# RASP_PICO_SCH.net
KiCad netlist of a schematic drawn in Altium Designer
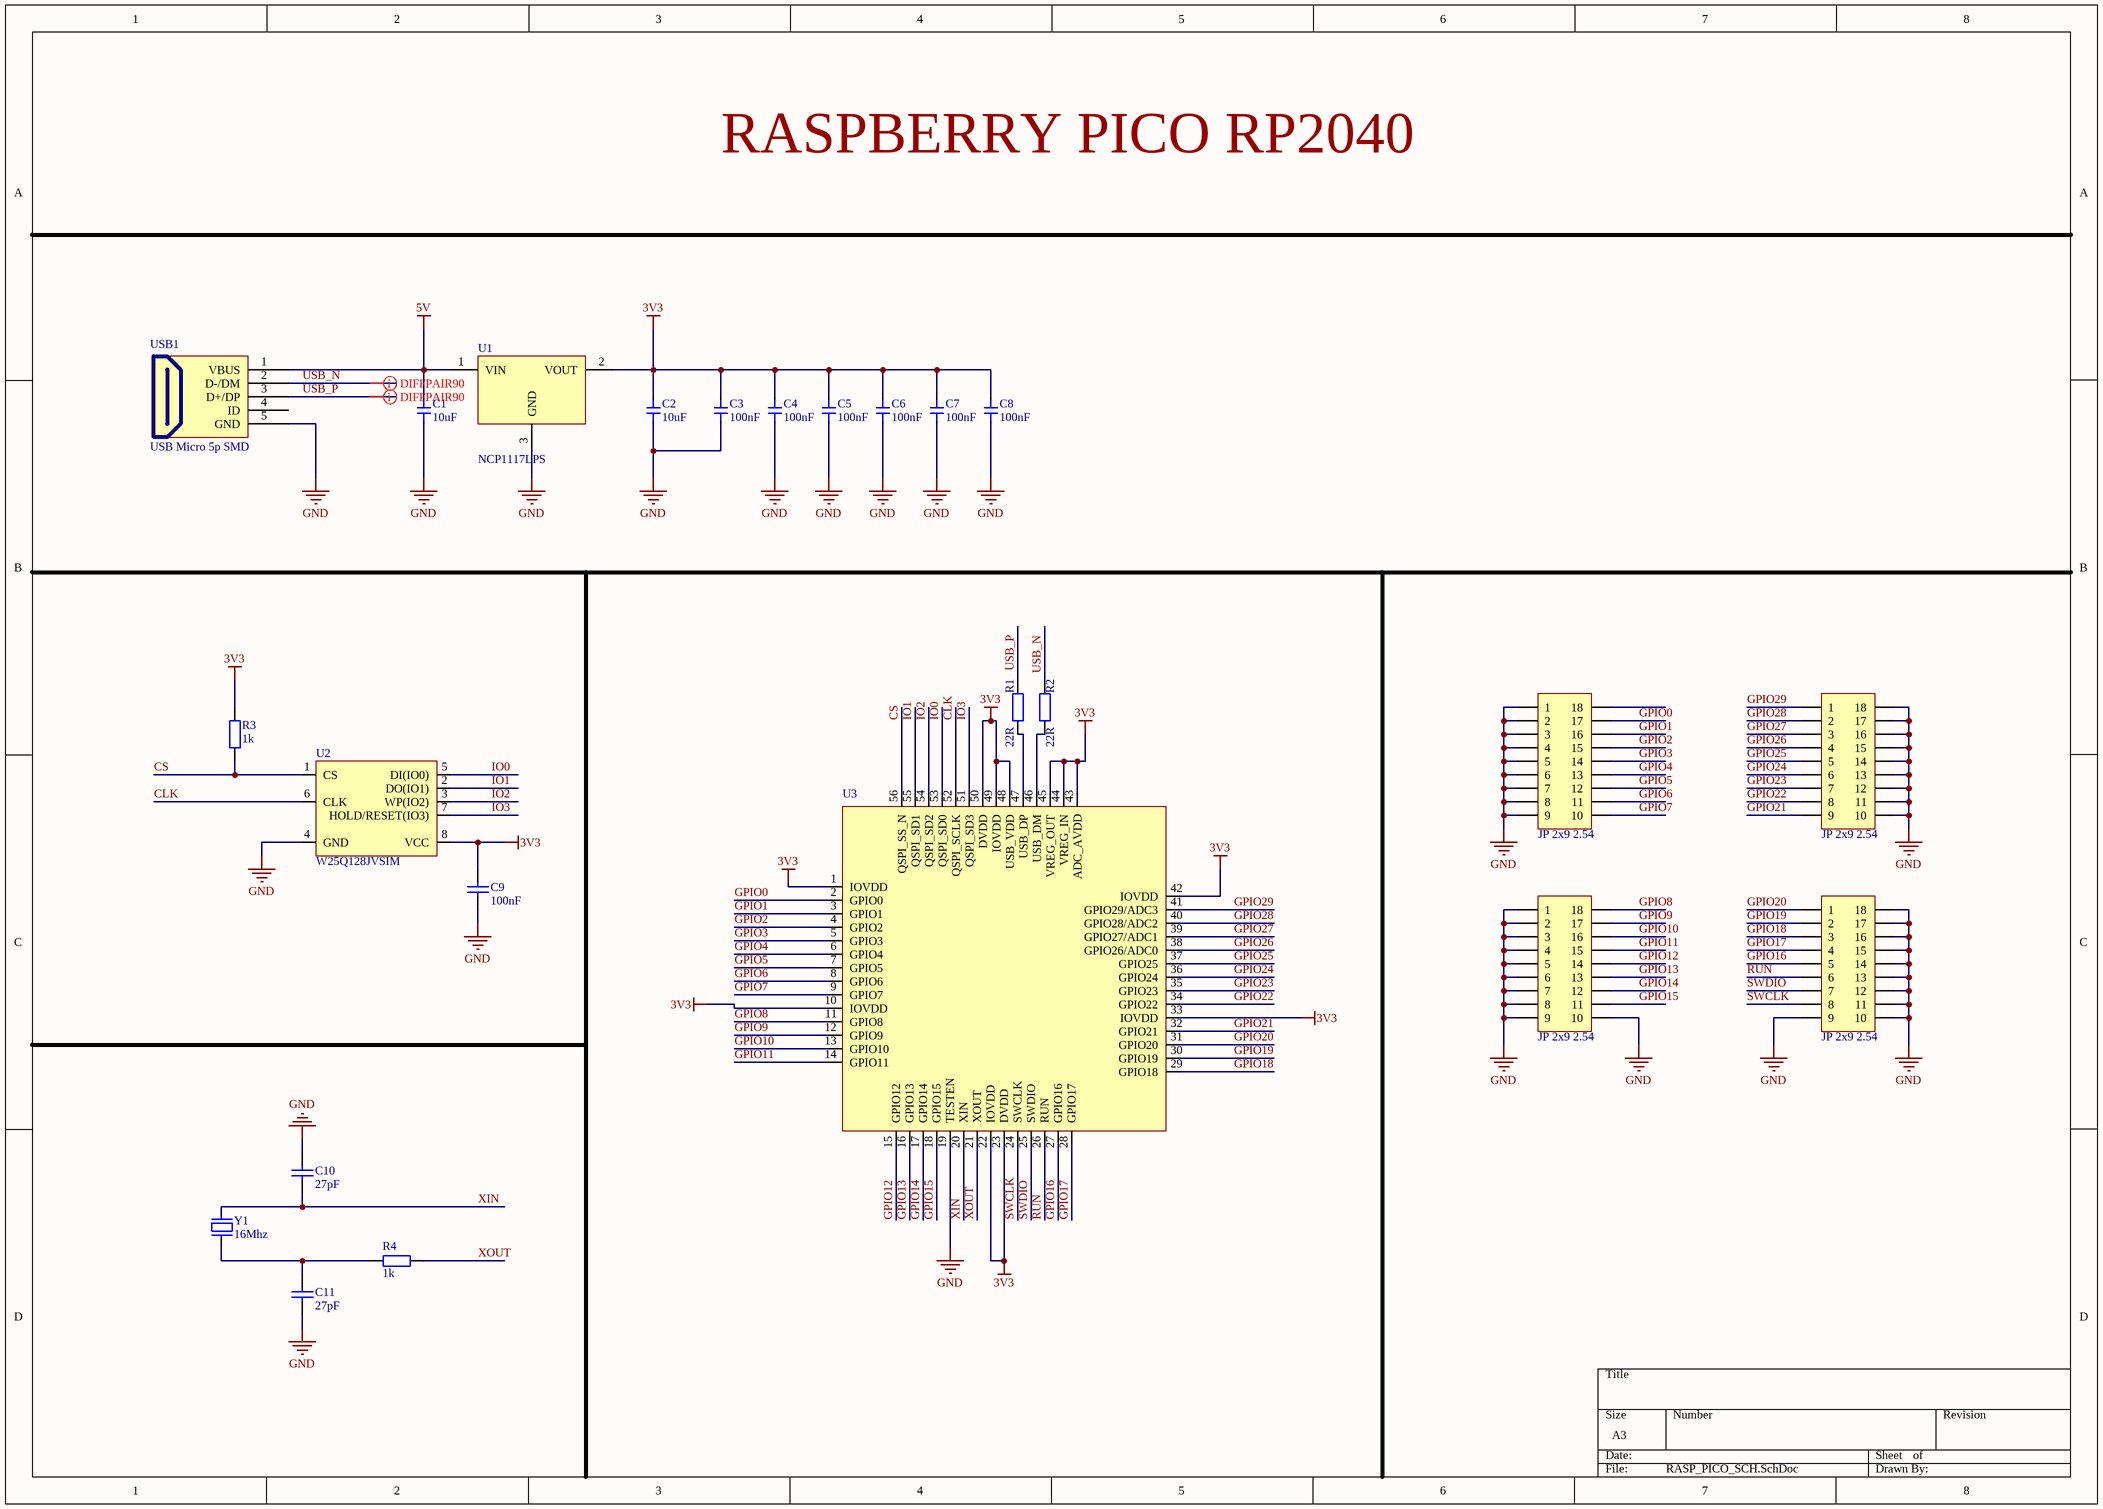
[diagram p0: RASP_PICO_SCH.SchDoc]

(export (version "E")
  (design (tool "Eeschema 10.0.6"))
  (components
    (comp (ref "C1")
      (value "10uF")
      (footprint "Cap 0805")
      (description "Capacitor SMD 0805")
      (libsource (lib "Altium_Lib_by_KhueNguyenCreator") (part "Cap 0805"))
    )
    (comp (ref "C2")
      (value "10uF")
      (footprint "Cap 0805")
      (description "Capacitor SMD 0805")
      (libsource (lib "Altium_Lib_by_KhueNguyenCreator") (part "Cap 0805"))
    )
    (comp (ref "C3")
      (value "100nF")
      (footprint "Cap 0805")
      (description "Capacitor SMD 0805")
      (libsource (lib "Altium_Lib_by_KhueNguyenCreator") (part "Cap 0805"))
    )
    (comp (ref "C4")
      (value "100nF")
      (footprint "Cap 0805")
      (description "Capacitor SMD 0805")
      (libsource (lib "Altium_Lib_by_KhueNguyenCreator") (part "Cap 0805"))
    )
    (comp (ref "C5")
      (value "100nF")
      (footprint "Cap 0805")
      (description "Capacitor SMD 0805")
      (libsource (lib "Altium_Lib_by_KhueNguyenCreator") (part "Cap 0805"))
    )
    (comp (ref "C6")
      (value "100nF")
      (footprint "Cap 0805")
      (description "Capacitor SMD 0805")
      (libsource (lib "Altium_Lib_by_KhueNguyenCreator") (part "Cap 0805"))
    )
    (comp (ref "C7")
      (value "100nF")
      (footprint "Cap 0805")
      (description "Capacitor SMD 0805")
      (libsource (lib "Altium_Lib_by_KhueNguyenCreator") (part "Cap 0805"))
    )
    (comp (ref "C8")
      (value "100nF")
      (footprint "Cap 0805")
      (description "Capacitor SMD 0805")
      (libsource (lib "Altium_Lib_by_KhueNguyenCreator") (part "Cap 0805"))
    )
    (comp (ref "C9")
      (value "100nF")
      (footprint "tu 0805")
      (description "Dán")
      (libsource (lib "Altium_Lib_by_KhueNguyenCreator") (part "Tu 0805 101 50V 20%"))
    )
    (comp (ref "C10")
      (value "27pF")
      (footprint "tu 0805")
      (description "Dán")
      (libsource (lib "Altium_Lib_by_KhueNguyenCreator") (part "Tu 0805 101 50V 20%"))
    )
    (comp (ref "C11")
      (value "27pF")
      (footprint "tu 0805")
      (description "Dán")
      (libsource (lib "Altium_Lib_by_KhueNguyenCreator") (part "Tu 0805 101 50V 20%"))
    )
    (comp (ref "JP1")
      (value "JP 2x9 2.54")
      (footprint "JP 2x9 DT")
      (description "Cắm")
      (libsource (lib "Altium_Lib_by_KhueNguyenCreator") (part "JP 2x9 2.54 Duc Thang"))
    )
    (comp (ref "JP2")
      (value "JP 2x9 2.54")
      (footprint "JP 2x9 DT")
      (description "Cắm")
      (libsource (lib "Altium_Lib_by_KhueNguyenCreator") (part "JP 2x9 2.54 Duc Thang"))
    )
    (comp (ref "JP3")
      (value "JP 2x9 2.54")
      (footprint "JP 2x9 DT")
      (description "Cắm")
      (libsource (lib "Altium_Lib_by_KhueNguyenCreator") (part "JP 2x9 2.54 Duc Thang"))
    )
    (comp (ref "JP4")
      (value "JP 2x9 2.54")
      (footprint "JP 2x9 DT")
      (description "Cắm")
      (libsource (lib "Altium_Lib_by_KhueNguyenCreator") (part "JP 2x9 2.54 Duc Thang"))
    )
    (comp (ref "R1")
      (value "22R")
      (footprint "tro smd 0805")
      (description "Dán")
      (libsource (lib "Altium_Lib_by_KhueNguyenCreator") (part "Tro 0805 5% 22R"))
    )
    (comp (ref "R2")
      (value "22R")
      (footprint "tro smd 0805")
      (description "Dán")
      (libsource (lib "Altium_Lib_by_KhueNguyenCreator") (part "Tro 0805 5% 22R"))
    )
    (comp (ref "R3")
      (value "1k")
      (footprint "tro smd 0805")
      (description "Dán")
      (libsource (lib "Altium_Lib_by_KhueNguyenCreator") (part "Tro 0805 1% 1k"))
    )
    (comp (ref "R4")
      (value "1k")
      (footprint "tro smd 0805")
      (description "Dán")
      (libsource (lib "Altium_Lib_by_KhueNguyenCreator") (part "Tro 0805 1% 1k"))
    )
    (comp (ref "U1")
      (value "NCP1117LPS")
      (footprint "SOT-223")
      (description "IC 3V3")
      (libsource (lib "SCH_LIB") (part "NCP1117LPS"))
    )
    (comp (ref "U2")
      (value "W25Q128JVSIM")
      (footprint "SOIC127P790X216-8N")
      (description "NOR Flash Serial (SPI, Dual SPI, Quad SPI) 3V/3.3V 128M-bit 16M x 8 6ns 8-Pin SOIC Tube")
      (fields (field (name "MANUFACTURER") "Winbond"))
      (libsource (lib "SCH_LIB") (part "W25Q128JVSIM"))
    )
    (comp (ref "U3")
      (value "RP2040TR7")
      (footprint "QFN40P700X700X90_HS-57N")
      (libsource (lib "SCH_LIB") (part "RP2040TR7"))
    )
    (comp (ref "USB1")
      (value "USB Micro 5p SMD")
      (footprint "USB Micro 5p SMD")
      (description "USB Type B")
      (libsource (lib "Altium_Lib_by_KhueNguyenCreator") (part "USB Micro 5p SMD"))
    )
    (comp (ref "Y1")
      (value "16Mhz")
      (footprint "Thach Anh 2 chan SMD5032")
      (description "Crystal For all Crystal 2pin.")
      (libsource (lib "Altium_Lib_by_KhueNguyenCreator") (part "Thach Anh 2 chan SMD 5032"))
    )
  )
  (nets
    (net (code "1") (name "/CLK") (class "Default")
      (node (ref "U2") (pin "6") (pinfunction "CLK_6") (pintype "passive"))
      (node (ref "U3") (pin "52") (pinfunction "QSPI_SCLK_52") (pintype "passive"))
    )
    (net (code "2") (name "/CS") (class "Default")
      (node (ref "R3") (pin "1") (pinfunction "1_1") (pintype "passive"))
      (node (ref "U2") (pin "1") (pinfunction "CS_1") (pintype "passive"))
      (node (ref "U3") (pin "56") (pinfunction "QSPI_SS_N_56") (pintype "passive"))
    )
    (net (code "3") (name "/GPIO0") (class "Default")
      (node (ref "JP1") (pin "17") (pinfunction "17_17") (pintype "passive"))
      (node (ref "U3") (pin "2") (pinfunction "GPIO0_2") (pintype "passive"))
    )
    (net (code "4") (name "/GPIO1") (class "Default")
      (node (ref "JP1") (pin "16") (pinfunction "16_16") (pintype "passive"))
      (node (ref "U3") (pin "3") (pinfunction "GPIO1_3") (pintype "passive"))
    )
    (net (code "5") (name "/GPIO2") (class "Default")
      (node (ref "JP1") (pin "15") (pinfunction "15_15") (pintype "passive"))
      (node (ref "U3") (pin "4") (pinfunction "GPIO2_4") (pintype "passive"))
    )
    (net (code "6") (name "/GPIO3") (class "Default")
      (node (ref "JP1") (pin "14") (pinfunction "14_14") (pintype "passive"))
      (node (ref "U3") (pin "5") (pinfunction "GPIO3_5") (pintype "passive"))
    )
    (net (code "7") (name "/GPIO4") (class "Default")
      (node (ref "JP1") (pin "13") (pinfunction "13_13") (pintype "passive"))
      (node (ref "U3") (pin "6") (pinfunction "GPIO4_6") (pintype "passive"))
    )
    (net (code "8") (name "/GPIO5") (class "Default")
      (node (ref "JP1") (pin "12") (pinfunction "12_12") (pintype "passive"))
      (node (ref "U3") (pin "7") (pinfunction "GPIO5_7") (pintype "passive"))
    )
    (net (code "9") (name "/GPIO6") (class "Default")
      (node (ref "JP1") (pin "11") (pinfunction "11_11") (pintype "passive"))
      (node (ref "U3") (pin "8") (pinfunction "GPIO6_8") (pintype "passive"))
    )
    (net (code "10") (name "/GPIO7") (class "Default")
      (node (ref "JP1") (pin "10") (pinfunction "10_10") (pintype "passive"))
      (node (ref "U3") (pin "9") (pinfunction "GPIO7_9") (pintype "passive"))
    )
    (net (code "11") (name "/GPIO8") (class "Default")
      (node (ref "JP3") (pin "18") (pinfunction "18_18") (pintype "passive"))
      (node (ref "U3") (pin "11") (pinfunction "GPIO8_11") (pintype "passive"))
    )
    (net (code "12") (name "/GPIO9") (class "Default")
      (node (ref "JP3") (pin "17") (pinfunction "17_17") (pintype "passive"))
      (node (ref "U3") (pin "12") (pinfunction "GPIO9_12") (pintype "passive"))
    )
    (net (code "13") (name "/GPIO10") (class "Default")
      (node (ref "JP3") (pin "16") (pinfunction "16_16") (pintype "passive"))
      (node (ref "U3") (pin "13") (pinfunction "GPIO10_13") (pintype "passive"))
    )
    (net (code "14") (name "/GPIO11") (class "Default")
      (node (ref "JP3") (pin "15") (pinfunction "15_15") (pintype "passive"))
      (node (ref "U3") (pin "14") (pinfunction "GPIO11_14") (pintype "passive"))
    )
    (net (code "15") (name "/GPIO12") (class "Default")
      (node (ref "JP3") (pin "14") (pinfunction "14_14") (pintype "passive"))
      (node (ref "U3") (pin "15") (pinfunction "GPIO12_15") (pintype "passive"))
    )
    (net (code "16") (name "/GPIO13") (class "Default")
      (node (ref "JP3") (pin "13") (pinfunction "13_13") (pintype "passive"))
      (node (ref "U3") (pin "16") (pinfunction "GPIO13_16") (pintype "passive"))
    )
    (net (code "17") (name "/GPIO14") (class "Default")
      (node (ref "JP3") (pin "12") (pinfunction "12_12") (pintype "passive"))
      (node (ref "U3") (pin "17") (pinfunction "GPIO14_17") (pintype "passive"))
    )
    (net (code "18") (name "/GPIO15") (class "Default")
      (node (ref "JP3") (pin "11") (pinfunction "11_11") (pintype "passive"))
      (node (ref "U3") (pin "18") (pinfunction "GPIO15_18") (pintype "passive"))
    )
    (net (code "19") (name "/GPIO16") (class "Default")
      (node (ref "JP4") (pin "5") (pinfunction "5_5") (pintype "passive"))
      (node (ref "U3") (pin "27") (pinfunction "GPIO16_27") (pintype "passive"))
    )
    (net (code "20") (name "/GPIO17") (class "Default")
      (node (ref "JP4") (pin "4") (pinfunction "4_4") (pintype "passive"))
      (node (ref "U3") (pin "28") (pinfunction "GPIO17_28") (pintype "passive"))
    )
    (net (code "21") (name "/GPIO18") (class "Default")
      (node (ref "JP4") (pin "3") (pinfunction "3_3") (pintype "passive"))
      (node (ref "U3") (pin "29") (pinfunction "GPIO18_29") (pintype "passive"))
    )
    (net (code "22") (name "/GPIO19") (class "Default")
      (node (ref "JP4") (pin "2") (pinfunction "2_2") (pintype "passive"))
      (node (ref "U3") (pin "30") (pinfunction "GPIO19_30") (pintype "passive"))
    )
    (net (code "23") (name "/GPIO20") (class "Default")
      (node (ref "JP4") (pin "1") (pinfunction "1_1") (pintype "passive"))
      (node (ref "U3") (pin "31") (pinfunction "GPIO20_31") (pintype "passive"))
    )
    (net (code "24") (name "/GPIO21") (class "Default")
      (node (ref "JP2") (pin "9") (pinfunction "9_9") (pintype "passive"))
      (node (ref "U3") (pin "32") (pinfunction "GPIO21_32") (pintype "passive"))
    )
    (net (code "25") (name "/GPIO22") (class "Default")
      (node (ref "JP2") (pin "8") (pinfunction "8_8") (pintype "passive"))
      (node (ref "U3") (pin "34") (pinfunction "GPIO22_34") (pintype "passive"))
    )
    (net (code "26") (name "/GPIO23") (class "Default")
      (node (ref "JP2") (pin "7") (pinfunction "7_7") (pintype "passive"))
      (node (ref "U3") (pin "35") (pinfunction "GPIO23_35") (pintype "passive"))
    )
    (net (code "27") (name "/GPIO24") (class "Default")
      (node (ref "JP2") (pin "6") (pinfunction "6_6") (pintype "passive"))
      (node (ref "U3") (pin "36") (pinfunction "GPIO24_36") (pintype "passive"))
    )
    (net (code "28") (name "/GPIO25") (class "Default")
      (node (ref "JP2") (pin "5") (pinfunction "5_5") (pintype "passive"))
      (node (ref "U3") (pin "37") (pinfunction "GPIO25_37") (pintype "passive"))
    )
    (net (code "29") (name "/GPIO26") (class "Default")
      (node (ref "JP2") (pin "4") (pinfunction "4_4") (pintype "passive"))
      (node (ref "U3") (pin "38") (pinfunction "GPIO26/ADC0_38") (pintype "passive"))
    )
    (net (code "30") (name "/GPIO27") (class "Default")
      (node (ref "JP2") (pin "3") (pinfunction "3_3") (pintype "passive"))
      (node (ref "U3") (pin "39") (pinfunction "GPIO27/ADC1_39") (pintype "passive"))
    )
    (net (code "31") (name "/GPIO28") (class "Default")
      (node (ref "JP2") (pin "2") (pinfunction "2_2") (pintype "passive"))
      (node (ref "U3") (pin "40") (pinfunction "GPIO28/ADC2_40") (pintype "passive"))
    )
    (net (code "32") (name "/GPIO29") (class "Default")
      (node (ref "JP2") (pin "1") (pinfunction "1_1") (pintype "passive"))
      (node (ref "U3") (pin "41") (pinfunction "GPIO29/ADC3_41") (pintype "passive"))
    )
    (net (code "33") (name "/IO0") (class "Default")
      (node (ref "U2") (pin "5") (pinfunction "DI(IO0)_5") (pintype "passive"))
      (node (ref "U3") (pin "53") (pinfunction "QSPI_SD0_53") (pintype "passive"))
    )
    (net (code "34") (name "/IO1") (class "Default")
      (node (ref "U2") (pin "2") (pinfunction "DO(IO1)_2") (pintype "passive"))
      (node (ref "U3") (pin "55") (pinfunction "QSPI_SD1_55") (pintype "passive"))
    )
    (net (code "35") (name "/IO2") (class "Default")
      (node (ref "U2") (pin "3") (pinfunction "WP(IO2)_3") (pintype "passive"))
      (node (ref "U3") (pin "54") (pinfunction "QSPI_SD2_54") (pintype "passive"))
    )
    (net (code "36") (name "/IO3") (class "Default")
      (node (ref "U2") (pin "7") (pinfunction "HOLD/RESET(IO3)_7") (pintype "passive"))
      (node (ref "U3") (pin "51") (pinfunction "QSPI_SD3_51") (pintype "passive"))
    )
    (net (code "37") (name "/RUN") (class "Default")
      (node (ref "JP4") (pin "6") (pinfunction "6_6") (pintype "passive"))
      (node (ref "U3") (pin "26") (pinfunction "RUN_26") (pintype "passive"))
    )
    (net (code "38") (name "/SWCLK") (class "Default")
      (node (ref "JP4") (pin "8") (pinfunction "8_8") (pintype "passive"))
      (node (ref "U3") (pin "24") (pinfunction "SWCLK_24") (pintype "passive"))
    )
    (net (code "39") (name "/SWDIO") (class "Default")
      (node (ref "JP4") (pin "7") (pinfunction "7_7") (pintype "passive"))
      (node (ref "U3") (pin "25") (pinfunction "SWDIO_25") (pintype "passive"))
    )
    (net (code "40") (name "/USB_N") (class "Default")
      (node (ref "R2") (pin "2") (pinfunction "2_2") (pintype "passive"))
      (node (ref "USB1") (pin "2") (pinfunction "D-/DM_2") (pintype "passive"))
    )
    (net (code "41") (name "/USB_P") (class "Default")
      (node (ref "R1") (pin "2") (pinfunction "2_2") (pintype "passive"))
      (node (ref "USB1") (pin "3") (pinfunction "D+/DP_3") (pintype "passive"))
    )
    (net (code "42") (name "/XIN") (class "Default")
      (node (ref "C10") (pin "2") (pinfunction "2_2") (pintype "passive"))
      (node (ref "U3") (pin "20") (pinfunction "XIN_20") (pintype "passive"))
      (node (ref "Y1") (pin "2") (pinfunction "2_2") (pintype "passive"))
    )
    (net (code "43") (name "/XOUT") (class "Default")
      (node (ref "R4") (pin "2") (pinfunction "2_2") (pintype "passive"))
      (node (ref "U3") (pin "21") (pinfunction "XOUT_21") (pintype "passive"))
    )
    (net (code "44") (name "3V3") (class "Default")
      (node (ref "C2") (pin "1") (pinfunction "1_1") (pintype "passive"))
      (node (ref "C3") (pin "1") (pinfunction "1_1") (pintype "passive"))
      (node (ref "C4") (pin "1") (pinfunction "1_1") (pintype "passive"))
      (node (ref "C5") (pin "1") (pinfunction "1_1") (pintype "passive"))
      (node (ref "C6") (pin "1") (pinfunction "1_1") (pintype "passive"))
      (node (ref "C7") (pin "1") (pinfunction "1_1") (pintype "passive"))
      (node (ref "C8") (pin "1") (pinfunction "1_1") (pintype "passive"))
      (node (ref "C9") (pin "1") (pinfunction "1_1") (pintype "passive"))
      (node (ref "R3") (pin "2") (pinfunction "2_2") (pintype "passive"))
      (node (ref "U1") (pin "2") (pinfunction "VOUT_2") (pintype "passive"))
      (node (ref "U2") (pin "8") (pinfunction "VCC_8") (pintype "passive"))
      (node (ref "U3") (pin "1") (pinfunction "IOVDD_1") (pintype "passive"))
      (node (ref "U3") (pin "10") (pinfunction "IOVDD_10") (pintype "passive"))
      (node (ref "U3") (pin "22") (pinfunction "IOVDD_22") (pintype "passive"))
      (node (ref "U3") (pin "23") (pinfunction "DVDD_23") (pintype "passive"))
      (node (ref "U3") (pin "33") (pinfunction "IOVDD_33") (pintype "passive"))
      (node (ref "U3") (pin "42") (pinfunction "IOVDD_42") (pintype "passive"))
      (node (ref "U3") (pin "43") (pinfunction "ADC_AVDD_43") (pintype "passive"))
      (node (ref "U3") (pin "44") (pinfunction "VREG_IN_44") (pintype "passive"))
      (node (ref "U3") (pin "45") (pinfunction "VREG_OUT_45") (pintype "passive"))
      (node (ref "U3") (pin "48") (pinfunction "USB_VDD_48") (pintype "passive"))
      (node (ref "U3") (pin "49") (pinfunction "IOVDD_49") (pintype "passive"))
      (node (ref "U3") (pin "50") (pinfunction "DVDD_50") (pintype "passive"))
    )
    (net (code "45") (name "5V") (class "Default")
      (node (ref "C1") (pin "1") (pinfunction "1_1") (pintype "passive"))
      (node (ref "U1") (pin "1") (pinfunction "VIN_1") (pintype "passive"))
      (node (ref "USB1") (pin "1") (pinfunction "VBUS_1") (pintype "passive"))
    )
    (net (code "46") (name "GND") (class "Default")
      (node (ref "C1") (pin "2") (pinfunction "2_2") (pintype "passive"))
      (node (ref "C10") (pin "1") (pinfunction "1_1") (pintype "passive"))
      (node (ref "C11") (pin "2") (pinfunction "2_2") (pintype "passive"))
      (node (ref "C2") (pin "2") (pinfunction "2_2") (pintype "passive"))
      (node (ref "C3") (pin "2") (pinfunction "2_2") (pintype "passive"))
      (node (ref "C4") (pin "2") (pinfunction "2_2") (pintype "passive"))
      (node (ref "C5") (pin "2") (pinfunction "2_2") (pintype "passive"))
      (node (ref "C6") (pin "2") (pinfunction "2_2") (pintype "passive"))
      (node (ref "C7") (pin "2") (pinfunction "2_2") (pintype "passive"))
      (node (ref "C8") (pin "2") (pinfunction "2_2") (pintype "passive"))
      (node (ref "C9") (pin "2") (pinfunction "2_2") (pintype "passive"))
      (node (ref "JP1") (pin "1") (pinfunction "1_1") (pintype "passive"))
      (node (ref "JP1") (pin "2") (pinfunction "2_2") (pintype "passive"))
      (node (ref "JP1") (pin "3") (pinfunction "3_3") (pintype "passive"))
      (node (ref "JP1") (pin "4") (pinfunction "4_4") (pintype "passive"))
      (node (ref "JP1") (pin "5") (pinfunction "5_5") (pintype "passive"))
      (node (ref "JP1") (pin "6") (pinfunction "6_6") (pintype "passive"))
      (node (ref "JP1") (pin "7") (pinfunction "7_7") (pintype "passive"))
      (node (ref "JP1") (pin "8") (pinfunction "8_8") (pintype "passive"))
      (node (ref "JP1") (pin "9") (pinfunction "9_9") (pintype "passive"))
      (node (ref "JP2") (pin "10") (pinfunction "10_10") (pintype "passive"))
      (node (ref "JP2") (pin "11") (pinfunction "11_11") (pintype "passive"))
      (node (ref "JP2") (pin "12") (pinfunction "12_12") (pintype "passive"))
      (node (ref "JP2") (pin "13") (pinfunction "13_13") (pintype "passive"))
      (node (ref "JP2") (pin "14") (pinfunction "14_14") (pintype "passive"))
      (node (ref "JP2") (pin "15") (pinfunction "15_15") (pintype "passive"))
      (node (ref "JP2") (pin "16") (pinfunction "16_16") (pintype "passive"))
      (node (ref "JP2") (pin "17") (pinfunction "17_17") (pintype "passive"))
      (node (ref "JP2") (pin "18") (pinfunction "18_18") (pintype "passive"))
      (node (ref "JP3") (pin "1") (pinfunction "1_1") (pintype "passive"))
      (node (ref "JP3") (pin "10") (pinfunction "10_10") (pintype "passive"))
      (node (ref "JP3") (pin "2") (pinfunction "2_2") (pintype "passive"))
      (node (ref "JP3") (pin "3") (pinfunction "3_3") (pintype "passive"))
      (node (ref "JP3") (pin "4") (pinfunction "4_4") (pintype "passive"))
      (node (ref "JP3") (pin "5") (pinfunction "5_5") (pintype "passive"))
      (node (ref "JP3") (pin "6") (pinfunction "6_6") (pintype "passive"))
      (node (ref "JP3") (pin "7") (pinfunction "7_7") (pintype "passive"))
      (node (ref "JP3") (pin "8") (pinfunction "8_8") (pintype "passive"))
      (node (ref "JP3") (pin "9") (pinfunction "9_9") (pintype "passive"))
      (node (ref "JP4") (pin "10") (pinfunction "10_10") (pintype "passive"))
      (node (ref "JP4") (pin "11") (pinfunction "11_11") (pintype "passive"))
      (node (ref "JP4") (pin "12") (pinfunction "12_12") (pintype "passive"))
      (node (ref "JP4") (pin "13") (pinfunction "13_13") (pintype "passive"))
      (node (ref "JP4") (pin "14") (pinfunction "14_14") (pintype "passive"))
      (node (ref "JP4") (pin "15") (pinfunction "15_15") (pintype "passive"))
      (node (ref "JP4") (pin "16") (pinfunction "16_16") (pintype "passive"))
      (node (ref "JP4") (pin "17") (pinfunction "17_17") (pintype "passive"))
      (node (ref "JP4") (pin "18") (pinfunction "18_18") (pintype "passive"))
      (node (ref "JP4") (pin "9") (pinfunction "9_9") (pintype "passive"))
      (node (ref "U1") (pin "3") (pinfunction "GND_3") (pintype "passive"))
      (node (ref "U2") (pin "4") (pinfunction "GND_4") (pintype "passive"))
      (node (ref "U3") (pin "19") (pinfunction "TESTEN_19") (pintype "passive"))
      (node (ref "USB1") (pin "5") (pinfunction "GND_5") (pintype "passive"))
    )
    (net (code "47") (name "Net-(C11-Pad1)") (class "Default")
      (node (ref "C11") (pin "1") (pinfunction "1_1") (pintype "passive"))
      (node (ref "R4") (pin "1") (pinfunction "1_1") (pintype "passive"))
      (node (ref "Y1") (pin "1") (pinfunction "1_1") (pintype "passive"))
    )
    (net (code "48") (name "Net-(U3-USB_DM)") (class "Default")
      (node (ref "R2") (pin "1") (pinfunction "1_1") (pintype "passive"))
      (node (ref "U3") (pin "46") (pinfunction "USB_DM_46") (pintype "passive"))
    )
    (net (code "49") (name "Net-(U3-USB_DP)") (class "Default")
      (node (ref "R1") (pin "1") (pinfunction "1_1") (pintype "passive"))
      (node (ref "U3") (pin "47") (pinfunction "USB_DP_47") (pintype "passive"))
    )
    (net (code "50") (name "unconnected-(JP1-Pad18)") (class "Default")
      (node (ref "JP1") (pin "18") (pinfunction "18_18") (pintype "passive"))
    )
    (net (code "51") (name "unconnected-(USB1-ID-Pad4)") (class "Default")
      (node (ref "USB1") (pin "4") (pinfunction "ID_4") (pintype "passive"))
    )
  )
)
